# GrblPi_B.net
KiCad netlist of a schematic drawn in EAGLE
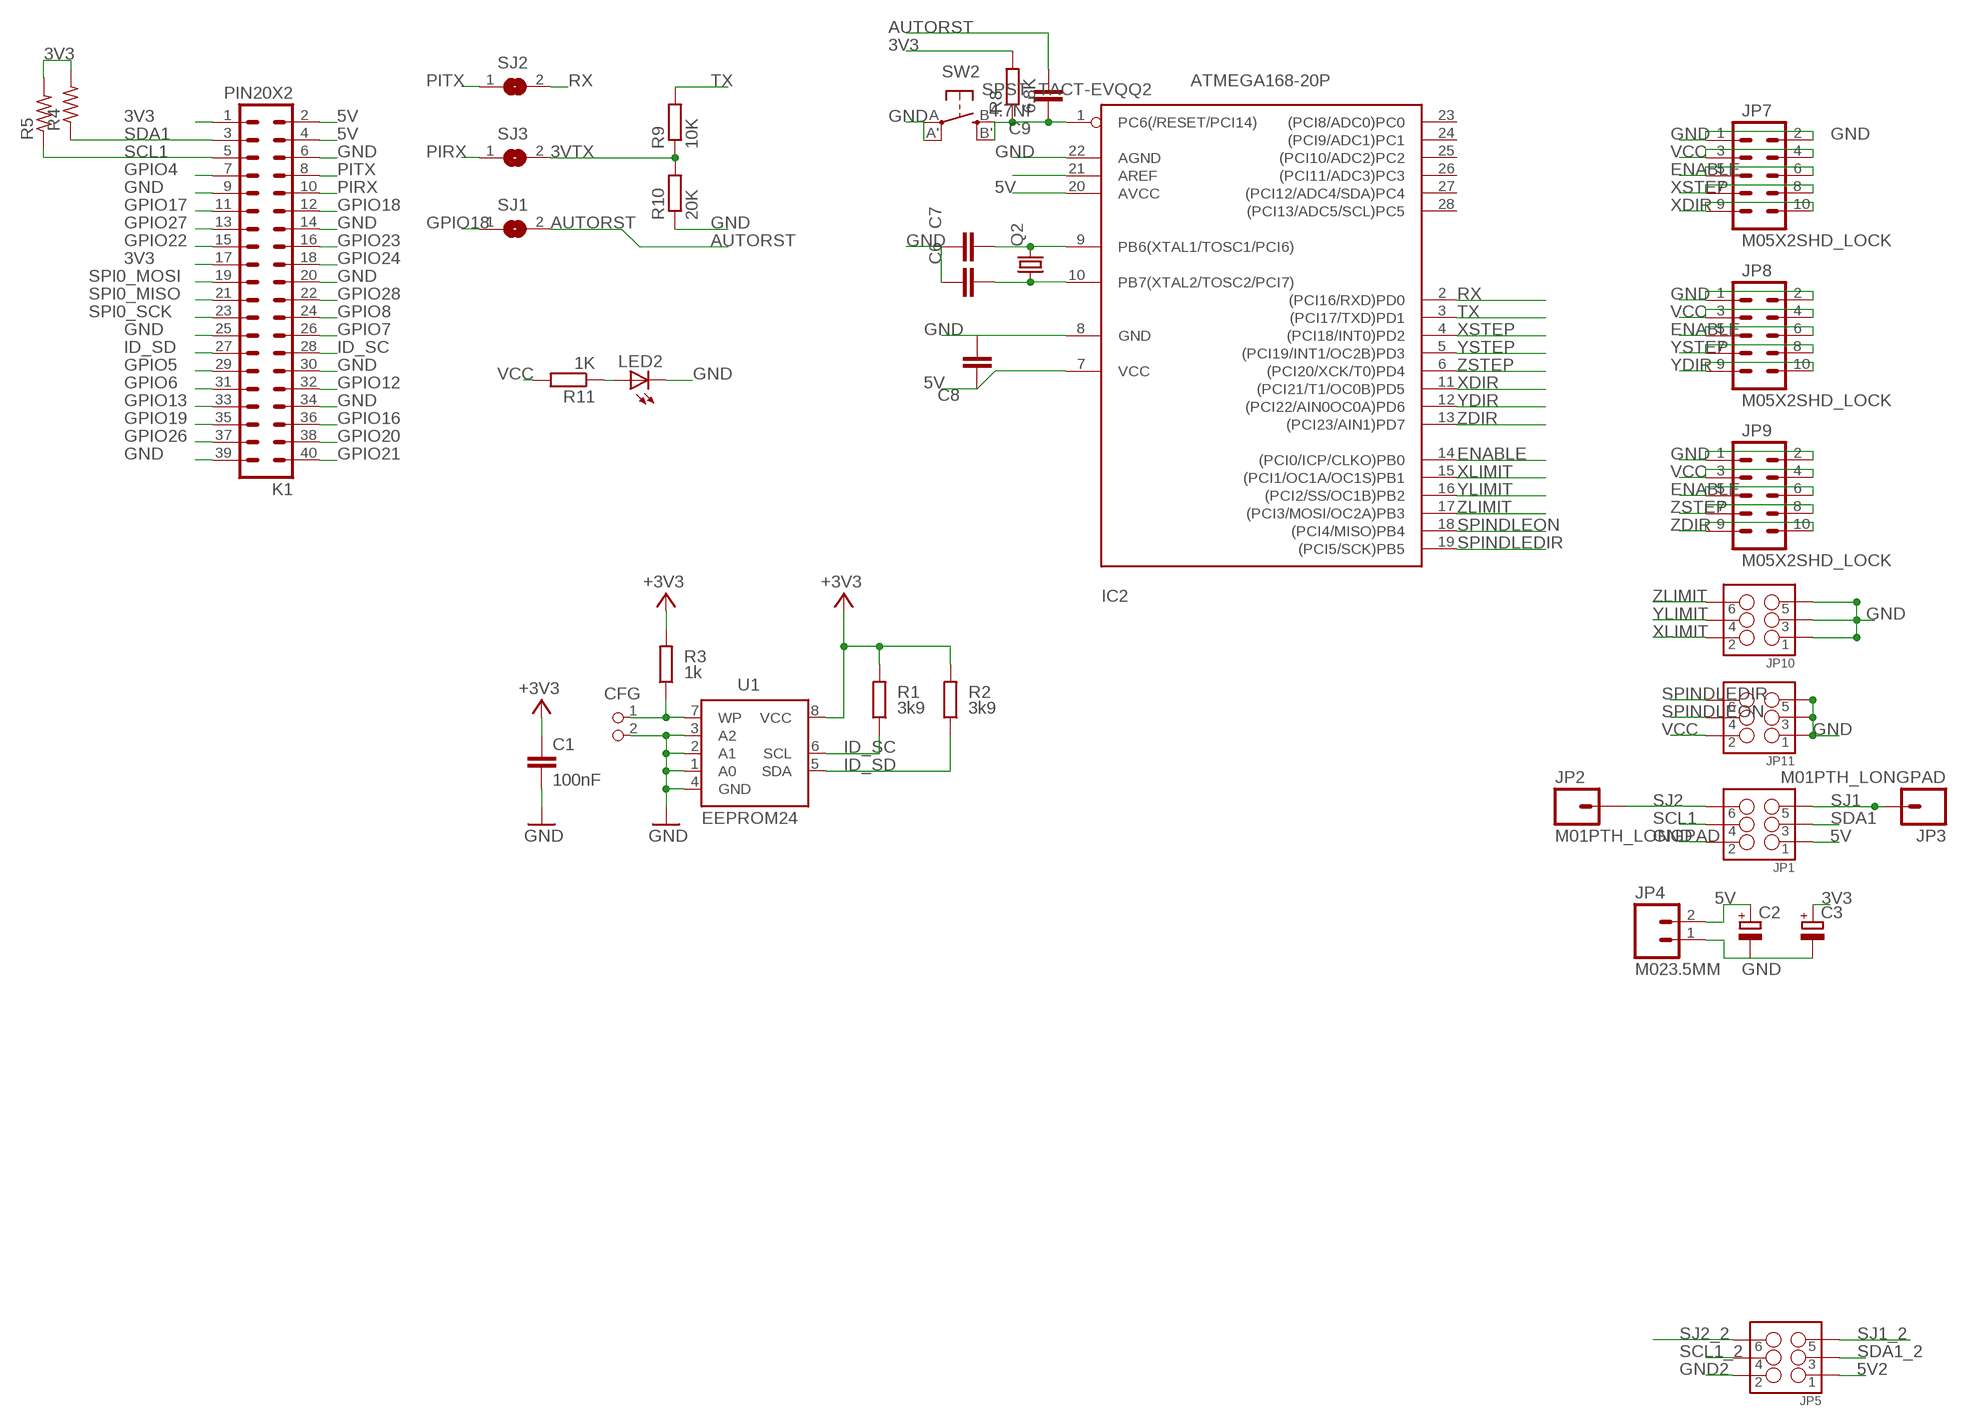
[diagram p0: schematic, sheet 1, part 1 of 2]
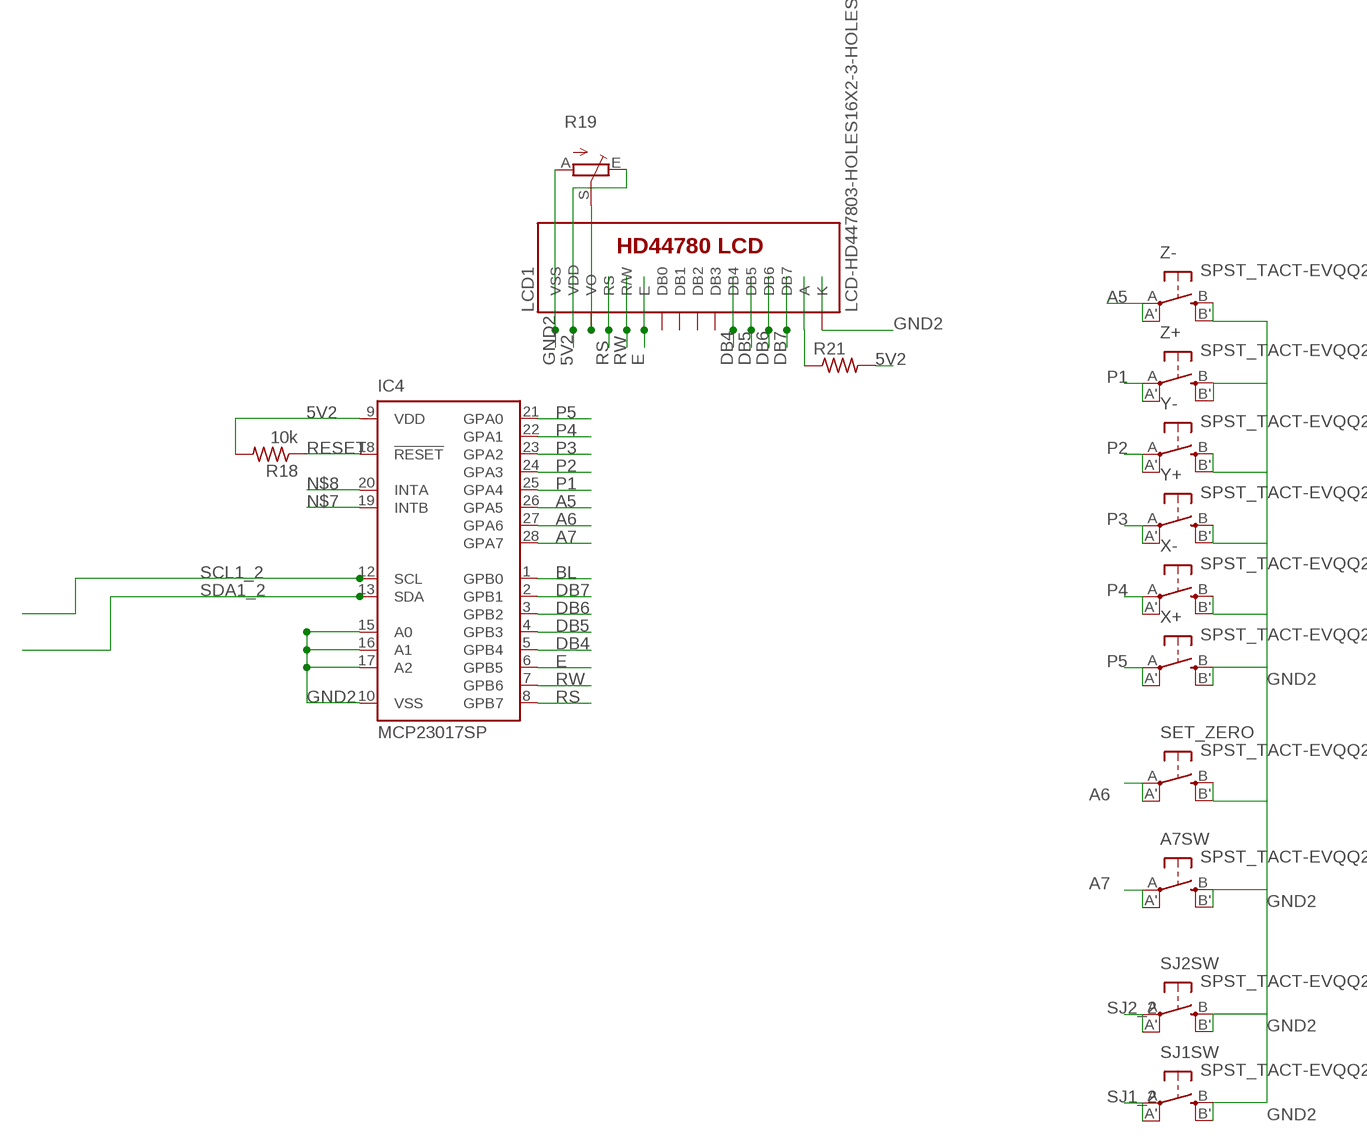
[diagram p1: schematic, sheet 1, part 2 of 2]

(export (version "E")
  (design (tool "Eeschema 10.0.6"))
  (components
    (comp (ref "A7SW")
      (value "SPST_TACT-EVQQ2")
      (footprint "eagle-import:EVQ-Q2")
      (libsource (lib "eagle-import") (part "SPST_TACT-EVQQ2"))
    )
    (comp (ref "C1")
      (value "100nF")
      (footprint "eagle-import:C1206")
      (libsource (lib "eagle-import") (part "C-EUC1206"))
    )
    (comp (ref "C2")
      (value "CPOL-EU153CLV-0405")
      (footprint "eagle-import:153CLV-0405")
      (libsource (lib "eagle-import") (part "CPOL-EU153CLV-0405"))
    )
    (comp (ref "C3")
      (value "CPOL-EU153CLV-0405")
      (footprint "eagle-import:153CLV-0405")
      (libsource (lib "eagle-import") (part "CPOL-EU153CLV-0405"))
    )
    (comp (ref "C6")
      (value "CAPACITOR_NPOL-1206")
      (footprint "eagle-import:C1206")
      (libsource (lib "eagle-import") (part "CAPACITOR_NPOL-1206"))
    )
    (comp (ref "C7")
      (value "CAPACITOR_NPOL-1206")
      (footprint "eagle-import:C1206")
      (libsource (lib "eagle-import") (part "CAPACITOR_NPOL-1206"))
    )
    (comp (ref "C8")
      (value "CAPACITOR_NPOL-1206")
      (footprint "eagle-import:C1206")
      (libsource (lib "eagle-import") (part "CAPACITOR_NPOL-1206"))
    )
    (comp (ref "C9")
      (value "4.7Nf")
      (footprint "eagle-import:C1206")
      (libsource (lib "eagle-import") (part "CAPACITOR_NPOL-1206"))
    )
    (comp (ref "CFG")
      (value "PIN2_100")
      (footprint "eagle-import:PIN_W_2")
      (libsource (lib "eagle-import") (part "PIN2_100"))
    )
    (comp (ref "IC2")
      (value "ATMEGA168-20P")
      (footprint "eagle-import:DIL28-3")
      (libsource (lib "eagle-import") (part "ATMEGA168P-20"))
    )
    (comp (ref "IC4")
      (value "MCP23017SP")
      (footprint "eagle-import:DIL28-3")
      (libsource (lib "eagle-import") (part "MCP23017SP"))
    )
    (comp (ref "JP1")
      (value "M03X2SHROUD")
      (footprint "eagle-import:2X3-SHROUDED")
      (libsource (lib "eagle-import") (part "M03X2SHROUD"))
    )
    (comp (ref "JP2")
      (value "M01PTH_LONGPAD")
      (footprint "eagle-import:1X01_LONGPAD")
      (libsource (lib "eagle-import") (part "M01PTH_LONGPAD"))
    )
    (comp (ref "JP3")
      (value "M01PTH_LONGPAD")
      (footprint "eagle-import:1X01_LONGPAD")
      (libsource (lib "eagle-import") (part "M01PTH_LONGPAD"))
    )
    (comp (ref "JP4")
      (value "M023.5MM")
      (footprint "eagle-import:SCREWTERMINAL-3.5MM-2")
      (libsource (lib "eagle-import") (part "M023.5MM"))
    )
    (comp (ref "JP5")
      (value "M03X2SHROUD")
      (footprint "eagle-import:2X3-SHROUDED")
      (libsource (lib "eagle-import") (part "M03X2SHROUD"))
    )
    (comp (ref "JP7")
      (value "M05X2SHD_LOCK")
      (footprint "eagle-import:2X5-SHROUDED_LOCK")
      (libsource (lib "eagle-import") (part "M05X2SHD_LOCK"))
    )
    (comp (ref "JP8")
      (value "M05X2SHD_LOCK")
      (footprint "eagle-import:2X5-SHROUDED_LOCK")
      (libsource (lib "eagle-import") (part "M05X2SHD_LOCK"))
    )
    (comp (ref "JP9")
      (value "M05X2SHD_LOCK")
      (footprint "eagle-import:2X5-SHROUDED_LOCK")
      (libsource (lib "eagle-import") (part "M05X2SHD_LOCK"))
    )
    (comp (ref "JP10")
      (value "M03X2SHROUD")
      (footprint "eagle-import:2X3-SHROUDED")
      (libsource (lib "eagle-import") (part "M03X2SHROUD"))
    )
    (comp (ref "JP11")
      (value "M03X2SHROUD")
      (footprint "eagle-import:2X3-SHROUDED")
      (libsource (lib "eagle-import") (part "M03X2SHROUD"))
    )
    (comp (ref "K1")
      (value "PIN20X2")
      (footprint "eagle-import:PIN_20X2")
      (libsource (lib "eagle-import") (part "PIN20X2"))
    )
    (comp (ref "LCD1")
      (value "LCD-HD447803-HOLES16X2-3-HOLES")
      (footprint "eagle-import:LCD-16X2-3HOLES")
      (libsource (lib "eagle-import") (part "LCD-HD4478016X2-3-HOLES3-HOLES"))
    )
    (comp (ref "LED2")
      (value "LEDCHIPLED_1206")
      (footprint "eagle-import:CHIPLED_1206")
      (libsource (lib "eagle-import") (part "LEDCHIPLED_1206"))
    )
    (comp (ref "Q2")
      (value "CRYSTALHC49UP")
      (footprint "eagle-import:HC49UP")
      (libsource (lib "eagle-import") (part "CRYSTALHC49UP"))
    )
    (comp (ref "R1")
      (value "3k9")
      (footprint "eagle-import:M1206")
      (fields (field (name "TOLERANCE") "5%"))
      (libsource (lib "eagle-import") (part "R-EU_M1206"))
    )
    (comp (ref "R2")
      (value "3k9")
      (footprint "eagle-import:M1206")
      (fields (field (name "TOLERANCE") "5%"))
      (libsource (lib "eagle-import") (part "R-EU_M1206"))
    )
    (comp (ref "R3")
      (value "1k")
      (footprint "eagle-import:M1206")
      (fields (field (name "TOLERANCE") "5%"))
      (libsource (lib "eagle-import") (part "R-EU_M1206"))
    )
    (comp (ref "R4")
      (value "R-US_M1206")
      (footprint "eagle-import:M1206")
      (libsource (lib "eagle-import") (part "R-US_M1206"))
    )
    (comp (ref "R5")
      (value "R-US_M1206")
      (footprint "eagle-import:M1206")
      (libsource (lib "eagle-import") (part "R-US_M1206"))
    )
    (comp (ref "R8")
      (value "6.8K")
      (footprint "eagle-import:R1206")
      (libsource (lib "eagle-import") (part "RESISTOR-1206"))
    )
    (comp (ref "R9")
      (value "10K")
      (footprint "eagle-import:R1206")
      (libsource (lib "eagle-import") (part "RESISTOR-1206"))
    )
    (comp (ref "R10")
      (value "20K")
      (footprint "eagle-import:R1206")
      (libsource (lib "eagle-import") (part "RESISTOR-1206"))
    )
    (comp (ref "R11")
      (value "1K")
      (footprint "eagle-import:R1206")
      (libsource (lib "eagle-import") (part "RESISTOR-1206"))
    )
    (comp (ref "R18")
      (value "10k")
      (footprint "eagle-import:M1206")
      (libsource (lib "eagle-import") (part "R-US_M1206"))
    )
    (comp (ref "R19")
      (value "TRIM_EU-CA6V")
      (footprint "eagle-import:CA6V")
      (libsource (lib "eagle-import") (part "TRIM_EU-CA6V"))
    )
    (comp (ref "R21")
      (value "R-US_M1206")
      (footprint "eagle-import:M1206")
      (libsource (lib "eagle-import") (part "R-US_M1206"))
    )
    (comp (ref "SET_ZERO")
      (value "SPST_TACT-EVQQ2")
      (footprint "eagle-import:EVQ-Q2")
      (libsource (lib "eagle-import") (part "SPST_TACT-EVQQ2"))
    )
    (comp (ref "SJ1") (value "SJ") (footprint "eagle-import:SJ") (libsource (lib "eagle-import") (part "SJ")))
    (comp (ref "SJ1SW")
      (value "SPST_TACT-EVQQ2")
      (footprint "eagle-import:EVQ-Q2")
      (libsource (lib "eagle-import") (part "SPST_TACT-EVQQ2"))
    )
    (comp (ref "SJ2") (value "SJ") (footprint "eagle-import:SJ") (libsource (lib "eagle-import") (part "SJ")))
    (comp (ref "SJ2SW")
      (value "SPST_TACT-EVQQ2")
      (footprint "eagle-import:EVQ-Q2")
      (libsource (lib "eagle-import") (part "SPST_TACT-EVQQ2"))
    )
    (comp (ref "SJ3") (value "SJ") (footprint "eagle-import:SJ") (libsource (lib "eagle-import") (part "SJ")))
    (comp (ref "SW2")
      (value "SPST_TACT-EVQQ2")
      (footprint "eagle-import:EVQ-Q2")
      (libsource (lib "eagle-import") (part "SPST_TACT-EVQQ2"))
    )
    (comp (ref "U1")
      (value "EEPROM24")
      (footprint "eagle-import:SOIC8")
      (libsource (lib "eagle-import") (part "EEPROM24"))
    )
    (comp (ref "X+")
      (value "SPST_TACT-EVQQ2")
      (footprint "eagle-import:EVQ-Q2")
      (libsource (lib "eagle-import") (part "SPST_TACT-EVQQ2"))
    )
    (comp (ref "X-")
      (value "SPST_TACT-EVQQ2")
      (footprint "eagle-import:EVQ-Q2")
      (libsource (lib "eagle-import") (part "SPST_TACT-EVQQ2"))
    )
    (comp (ref "Y+")
      (value "SPST_TACT-EVQQ2")
      (footprint "eagle-import:EVQ-Q2")
      (libsource (lib "eagle-import") (part "SPST_TACT-EVQQ2"))
    )
    (comp (ref "Y-")
      (value "SPST_TACT-EVQQ2")
      (footprint "eagle-import:EVQ-Q2")
      (libsource (lib "eagle-import") (part "SPST_TACT-EVQQ2"))
    )
    (comp (ref "Z+")
      (value "SPST_TACT-EVQQ2")
      (footprint "eagle-import:EVQ-Q2")
      (libsource (lib "eagle-import") (part "SPST_TACT-EVQQ2"))
    )
    (comp (ref "Z-")
      (value "SPST_TACT-EVQQ2")
      (footprint "eagle-import:EVQ-Q2")
      (libsource (lib "eagle-import") (part "SPST_TACT-EVQQ2"))
    )
  )
  (nets
    (net (code "1") (name "+3V3") (class "Default")
      (node (ref "C1") (pin "1") (pinfunction "1_1") (pintype "passive"))
      (node (ref "R1") (pin "2") (pinfunction "2_2") (pintype "passive"))
      (node (ref "R2") (pin "2") (pinfunction "2_2") (pintype "passive"))
      (node (ref "R3") (pin "2") (pinfunction "2_2") (pintype "passive"))
      (node (ref "U1") (pin "8") (pinfunction "VCC_8") (pintype "power_in"))
    )
    (net (code "2") (name "/3V3") (class "Default")
      (node (ref "C3") (pin "+") (pinfunction "+_+") (pintype "passive"))
      (node (ref "K1") (pin "1") (pinfunction "1_1") (pintype "passive"))
      (node (ref "K1") (pin "17") (pinfunction "17_17") (pintype "passive"))
      (node (ref "R4") (pin "2") (pinfunction "2_2") (pintype "passive"))
      (node (ref "R5") (pin "2") (pinfunction "2_2") (pintype "passive"))
      (node (ref "R8") (pin "2") (pinfunction "2_2") (pintype "passive"))
    )
    (net (code "3") (name "/3VTX") (class "Default")
      (node (ref "R10") (pin "2") (pinfunction "2_2") (pintype "passive"))
      (node (ref "R9") (pin "1") (pinfunction "1_1") (pintype "passive"))
      (node (ref "SJ3") (pin "2") (pinfunction "2_2") (pintype "passive"))
    )
    (net (code "4") (name "/5V") (class "Default")
      (node (ref "C2") (pin "+") (pinfunction "+_+") (pintype "passive"))
      (node (ref "C8") (pin "1") (pinfunction "1_1") (pintype "passive"))
      (node (ref "IC2") (pin "20") (pinfunction "AVCC_20") (pintype "bidirectional"))
      (node (ref "IC2") (pin "7") (pinfunction "VCC_7") (pintype "bidirectional"))
      (node (ref "JP1") (pin "1") (pinfunction "1_1") (pintype "bidirectional"))
      (node (ref "JP4") (pin "2") (pinfunction "2_2") (pintype "passive"))
      (node (ref "K1") (pin "2") (pinfunction "2_2") (pintype "passive"))
      (node (ref "K1") (pin "4") (pinfunction "4_4") (pintype "passive"))
    )
    (net (code "5") (name "/5V2") (class "Default")
      (node (ref "IC4") (pin "9") (pinfunction "VDD_9") (pintype "power_in"))
      (node (ref "JP5") (pin "1") (pinfunction "1_1") (pintype "bidirectional"))
      (node (ref "LCD1") (pin "2") (pinfunction "VDD_2") (pintype "power_in"))
      (node (ref "R18") (pin "2") (pinfunction "2_2") (pintype "passive"))
      (node (ref "R19") (pin "E") (pinfunction "E_E") (pintype "passive"))
      (node (ref "R21") (pin "2") (pinfunction "2_2") (pintype "passive"))
    )
    (net (code "6") (name "/A5") (class "Default")
      (node (ref "IC4") (pin "26") (pinfunction "GPA5_26") (pintype "bidirectional"))
      (node (ref "Z-") (pin "A") (pinfunction "P_A") (pintype "passive"))
      (node (ref "Z-") (pin "A'") (pinfunction "P1_A'") (pintype "passive"))
    )
    (net (code "7") (name "/A6") (class "Default")
      (node (ref "IC4") (pin "27") (pinfunction "GPA6_27") (pintype "bidirectional"))
      (node (ref "SET_ZERO") (pin "A") (pinfunction "P_A") (pintype "passive"))
      (node (ref "SET_ZERO") (pin "A'") (pinfunction "P1_A'") (pintype "passive"))
    )
    (net (code "8") (name "/A7") (class "Default")
      (node (ref "A7SW") (pin "A") (pinfunction "P_A") (pintype "passive"))
      (node (ref "A7SW") (pin "A'") (pinfunction "P1_A'") (pintype "passive"))
      (node (ref "IC4") (pin "28") (pinfunction "GPA7_28") (pintype "bidirectional"))
    )
    (net (code "9") (name "/AUTORST") (class "Default")
      (node (ref "C9") (pin "2") (pinfunction "2_2") (pintype "passive"))
      (node (ref "SJ1") (pin "2") (pinfunction "2_2") (pintype "passive"))
    )
    (net (code "10") (name "/BL") (class "Default")
      (node (ref "IC4") (pin "1") (pinfunction "GPB0_1") (pintype "bidirectional"))
    )
    (net (code "11") (name "/DB4") (class "Default")
      (node (ref "IC4") (pin "5") (pinfunction "GPB4_5") (pintype "bidirectional"))
      (node (ref "LCD1") (pin "11") (pinfunction "DB4_11") (pintype "bidirectional"))
    )
    (net (code "12") (name "/DB5") (class "Default")
      (node (ref "IC4") (pin "4") (pinfunction "GPB3_4") (pintype "bidirectional"))
      (node (ref "LCD1") (pin "12") (pinfunction "DB5_12") (pintype "bidirectional"))
    )
    (net (code "13") (name "/DB6") (class "Default")
      (node (ref "IC4") (pin "3") (pinfunction "GPB2_3") (pintype "bidirectional"))
      (node (ref "LCD1") (pin "13") (pinfunction "DB6_13") (pintype "bidirectional"))
    )
    (net (code "14") (name "/DB7") (class "Default")
      (node (ref "IC4") (pin "2") (pinfunction "GPB1_2") (pintype "bidirectional"))
      (node (ref "LCD1") (pin "14") (pinfunction "DB7_14") (pintype "bidirectional"))
    )
    (net (code "15") (name "/E") (class "Default")
      (node (ref "IC4") (pin "6") (pinfunction "GPB5_6") (pintype "bidirectional"))
      (node (ref "LCD1") (pin "6") (pinfunction "E_6") (pintype "input"))
    )
    (net (code "16") (name "/ENABLE") (class "Default")
      (node (ref "IC2") (pin "14") (pinfunction "(PCI0/ICP/CLKO)PB0_14") (pintype "bidirectional"))
      (node (ref "JP7") (pin "5") (pinfunction "5_5") (pintype "passive"))
      (node (ref "JP7") (pin "6") (pinfunction "6_6") (pintype "passive"))
      (node (ref "JP8") (pin "5") (pinfunction "5_5") (pintype "passive"))
      (node (ref "JP8") (pin "6") (pinfunction "6_6") (pintype "passive"))
      (node (ref "JP9") (pin "5") (pinfunction "5_5") (pintype "passive"))
      (node (ref "JP9") (pin "6") (pinfunction "6_6") (pintype "passive"))
    )
    (net (code "17") (name "/GND2") (class "Default")
      (node (ref "A7SW") (pin "B") (pinfunction "S_B") (pintype "passive"))
      (node (ref "A7SW") (pin "B'") (pinfunction "S1_B'") (pintype "passive"))
      (node (ref "IC4") (pin "10") (pinfunction "VSS_10") (pintype "power_in"))
      (node (ref "IC4") (pin "15") (pinfunction "A0_15") (pintype "input"))
      (node (ref "IC4") (pin "16") (pinfunction "A1_16") (pintype "input"))
      (node (ref "IC4") (pin "17") (pinfunction "A2_17") (pintype "input"))
      (node (ref "JP5") (pin "2") (pinfunction "2_2") (pintype "bidirectional"))
      (node (ref "LCD1") (pin "1") (pinfunction "VSS_1") (pintype "power_in"))
      (node (ref "LCD1") (pin "16") (pinfunction "K_16") (pintype "power_in"))
      (node (ref "R19") (pin "A") (pinfunction "A_A") (pintype "passive"))
      (node (ref "SET_ZERO") (pin "B") (pinfunction "S_B") (pintype "passive"))
      (node (ref "SET_ZERO") (pin "B'") (pinfunction "S1_B'") (pintype "passive"))
      (node (ref "SJ1SW") (pin "B") (pinfunction "S_B") (pintype "passive"))
      (node (ref "SJ1SW") (pin "B'") (pinfunction "S1_B'") (pintype "passive"))
      (node (ref "SJ2SW") (pin "B") (pinfunction "S_B") (pintype "passive"))
      (node (ref "SJ2SW") (pin "B'") (pinfunction "S1_B'") (pintype "passive"))
      (node (ref "X+") (pin "B") (pinfunction "S_B") (pintype "passive"))
      (node (ref "X+") (pin "B'") (pinfunction "S1_B'") (pintype "passive"))
      (node (ref "X-") (pin "B") (pinfunction "S_B") (pintype "passive"))
      (node (ref "X-") (pin "B'") (pinfunction "S1_B'") (pintype "passive"))
      (node (ref "Y+") (pin "B") (pinfunction "S_B") (pintype "passive"))
      (node (ref "Y+") (pin "B'") (pinfunction "S1_B'") (pintype "passive"))
      (node (ref "Y-") (pin "B") (pinfunction "S_B") (pintype "passive"))
      (node (ref "Y-") (pin "B'") (pinfunction "S1_B'") (pintype "passive"))
      (node (ref "Z+") (pin "B") (pinfunction "S_B") (pintype "passive"))
      (node (ref "Z+") (pin "B'") (pinfunction "S1_B'") (pintype "passive"))
      (node (ref "Z-") (pin "B") (pinfunction "S_B") (pintype "passive"))
      (node (ref "Z-") (pin "B'") (pinfunction "S1_B'") (pintype "passive"))
    )
    (net (code "18") (name "/GPIO4") (class "Default")
      (node (ref "K1") (pin "7") (pinfunction "7_7") (pintype "passive"))
    )
    (net (code "19") (name "/GPIO5") (class "Default")
      (node (ref "K1") (pin "29") (pinfunction "29_29") (pintype "passive"))
    )
    (net (code "20") (name "/GPIO6") (class "Default")
      (node (ref "K1") (pin "31") (pinfunction "31_31") (pintype "passive"))
    )
    (net (code "21") (name "/GPIO7") (class "Default")
      (node (ref "K1") (pin "26") (pinfunction "26_26") (pintype "passive"))
    )
    (net (code "22") (name "/GPIO8") (class "Default")
      (node (ref "K1") (pin "24") (pinfunction "24_24") (pintype "passive"))
    )
    (net (code "23") (name "/GPIO12") (class "Default")
      (node (ref "K1") (pin "32") (pinfunction "32_32") (pintype "passive"))
    )
    (net (code "24") (name "/GPIO13") (class "Default")
      (node (ref "K1") (pin "33") (pinfunction "33_33") (pintype "passive"))
    )
    (net (code "25") (name "/GPIO16") (class "Default")
      (node (ref "K1") (pin "36") (pinfunction "36_36") (pintype "passive"))
    )
    (net (code "26") (name "/GPIO17") (class "Default")
      (node (ref "K1") (pin "11") (pinfunction "11_11") (pintype "passive"))
    )
    (net (code "27") (name "/GPIO18") (class "Default")
      (node (ref "K1") (pin "12") (pinfunction "12_12") (pintype "passive"))
      (node (ref "SJ1") (pin "1") (pinfunction "1_1") (pintype "passive"))
    )
    (net (code "28") (name "/GPIO19") (class "Default")
      (node (ref "K1") (pin "35") (pinfunction "35_35") (pintype "passive"))
    )
    (net (code "29") (name "/GPIO20") (class "Default")
      (node (ref "K1") (pin "38") (pinfunction "38_38") (pintype "passive"))
    )
    (net (code "30") (name "/GPIO21") (class "Default")
      (node (ref "K1") (pin "40") (pinfunction "40_40") (pintype "passive"))
    )
    (net (code "31") (name "/GPIO22") (class "Default")
      (node (ref "K1") (pin "15") (pinfunction "15_15") (pintype "passive"))
    )
    (net (code "32") (name "/GPIO23") (class "Default")
      (node (ref "K1") (pin "16") (pinfunction "16_16") (pintype "passive"))
    )
    (net (code "33") (name "/GPIO24") (class "Default")
      (node (ref "K1") (pin "18") (pinfunction "18_18") (pintype "passive"))
    )
    (net (code "34") (name "/GPIO26") (class "Default")
      (node (ref "K1") (pin "37") (pinfunction "37_37") (pintype "passive"))
    )
    (net (code "35") (name "/GPIO27") (class "Default")
      (node (ref "K1") (pin "13") (pinfunction "13_13") (pintype "passive"))
    )
    (net (code "36") (name "/GPIO28") (class "Default")
      (node (ref "K1") (pin "22") (pinfunction "22_22") (pintype "passive"))
    )
    (net (code "37") (name "/ID_SC") (class "Default")
      (node (ref "K1") (pin "28") (pinfunction "28_28") (pintype "passive"))
      (node (ref "R1") (pin "1") (pinfunction "1_1") (pintype "passive"))
      (node (ref "U1") (pin "6") (pinfunction "SCL_6") (pintype "input"))
    )
    (net (code "38") (name "/ID_SD") (class "Default")
      (node (ref "K1") (pin "27") (pinfunction "27_27") (pintype "passive"))
      (node (ref "R2") (pin "1") (pinfunction "1_1") (pintype "passive"))
      (node (ref "U1") (pin "5") (pinfunction "SDA_5") (pintype "bidirectional"))
    )
    (net (code "39") (name "/N$7") (class "Default")
      (node (ref "IC4") (pin "19") (pinfunction "INTB_19") (pintype "output"))
    )
    (net (code "40") (name "/N$8") (class "Default")
      (node (ref "IC4") (pin "20") (pinfunction "INTA_20") (pintype "output"))
    )
    (net (code "41") (name "/P1") (class "Default")
      (node (ref "IC4") (pin "25") (pinfunction "GPA4_25") (pintype "bidirectional"))
      (node (ref "Z+") (pin "A") (pinfunction "P_A") (pintype "passive"))
      (node (ref "Z+") (pin "A'") (pinfunction "P1_A'") (pintype "passive"))
    )
    (net (code "42") (name "/P2") (class "Default")
      (node (ref "IC4") (pin "24") (pinfunction "GPA3_24") (pintype "bidirectional"))
      (node (ref "Y-") (pin "A") (pinfunction "P_A") (pintype "passive"))
      (node (ref "Y-") (pin "A'") (pinfunction "P1_A'") (pintype "passive"))
    )
    (net (code "43") (name "/P3") (class "Default")
      (node (ref "IC4") (pin "23") (pinfunction "GPA2_23") (pintype "bidirectional"))
      (node (ref "Y+") (pin "A") (pinfunction "P_A") (pintype "passive"))
      (node (ref "Y+") (pin "A'") (pinfunction "P1_A'") (pintype "passive"))
    )
    (net (code "44") (name "/P4") (class "Default")
      (node (ref "IC4") (pin "22") (pinfunction "GPA1_22") (pintype "bidirectional"))
      (node (ref "X-") (pin "A") (pinfunction "P_A") (pintype "passive"))
      (node (ref "X-") (pin "A'") (pinfunction "P1_A'") (pintype "passive"))
    )
    (net (code "45") (name "/P5") (class "Default")
      (node (ref "IC4") (pin "21") (pinfunction "GPA0_21") (pintype "bidirectional"))
      (node (ref "X+") (pin "A") (pinfunction "P_A") (pintype "passive"))
      (node (ref "X+") (pin "A'") (pinfunction "P1_A'") (pintype "passive"))
    )
    (net (code "46") (name "/PIRX") (class "Default")
      (node (ref "K1") (pin "10") (pinfunction "10_10") (pintype "passive"))
      (node (ref "SJ3") (pin "1") (pinfunction "1_1") (pintype "passive"))
    )
    (net (code "47") (name "/PITX") (class "Default")
      (node (ref "K1") (pin "8") (pinfunction "8_8") (pintype "passive"))
      (node (ref "SJ2") (pin "1") (pinfunction "1_1") (pintype "passive"))
    )
    (net (code "48") (name "/RESET") (class "Default")
      (node (ref "IC4") (pin "18") (pinfunction "~{RESET}_18") (pintype "input"))
      (node (ref "R18") (pin "1") (pinfunction "1_1") (pintype "passive"))
    )
    (net (code "49") (name "/RS") (class "Default")
      (node (ref "IC4") (pin "8") (pinfunction "GPB7_8") (pintype "bidirectional"))
      (node (ref "LCD1") (pin "4") (pinfunction "RS_4") (pintype "input"))
    )
    (net (code "50") (name "/RW") (class "Default")
      (node (ref "IC4") (pin "7") (pinfunction "GPB6_7") (pintype "bidirectional"))
      (node (ref "LCD1") (pin "5") (pinfunction "R/W_5") (pintype "input"))
    )
    (net (code "51") (name "/RX") (class "Default")
      (node (ref "IC2") (pin "2") (pinfunction "(PCI16/RXD)PD0_2") (pintype "bidirectional"))
      (node (ref "SJ2") (pin "2") (pinfunction "2_2") (pintype "passive"))
    )
    (net (code "52") (name "/SCL1") (class "Default")
      (node (ref "JP1") (pin "4") (pinfunction "4_4") (pintype "bidirectional"))
      (node (ref "K1") (pin "5") (pinfunction "5_5") (pintype "passive"))
      (node (ref "R5") (pin "1") (pinfunction "1_1") (pintype "passive"))
    )
    (net (code "53") (name "/SCL1_2") (class "Default")
      (node (ref "IC4") (pin "12") (pinfunction "SCL_12") (pintype "input"))
      (node (ref "JP5") (pin "4") (pinfunction "4_4") (pintype "bidirectional"))
    )
    (net (code "54") (name "/SDA1") (class "Default")
      (node (ref "JP1") (pin "3") (pinfunction "3_3") (pintype "bidirectional"))
      (node (ref "K1") (pin "3") (pinfunction "3_3") (pintype "passive"))
      (node (ref "R4") (pin "1") (pinfunction "1_1") (pintype "passive"))
    )
    (net (code "55") (name "/SDA1_2") (class "Default")
      (node (ref "IC4") (pin "13") (pinfunction "SDA_13") (pintype "bidirectional"))
      (node (ref "JP5") (pin "3") (pinfunction "3_3") (pintype "bidirectional"))
    )
    (net (code "56") (name "/SJ1") (class "Default")
      (node (ref "JP1") (pin "5") (pinfunction "5_5") (pintype "bidirectional"))
      (node (ref "JP3") (pin "1") (pinfunction "1_1") (pintype "passive"))
    )
    (net (code "57") (name "/SJ1_2") (class "Default")
      (node (ref "JP5") (pin "5") (pinfunction "5_5") (pintype "bidirectional"))
      (node (ref "SJ1SW") (pin "A") (pinfunction "P_A") (pintype "passive"))
      (node (ref "SJ1SW") (pin "A'") (pinfunction "P1_A'") (pintype "passive"))
    )
    (net (code "58") (name "/SJ2") (class "Default")
      (node (ref "JP1") (pin "6") (pinfunction "6_6") (pintype "bidirectional"))
      (node (ref "JP2") (pin "1") (pinfunction "1_1") (pintype "passive"))
    )
    (net (code "59") (name "/SJ2_2") (class "Default")
      (node (ref "JP5") (pin "6") (pinfunction "6_6") (pintype "bidirectional"))
      (node (ref "SJ2SW") (pin "A") (pinfunction "P_A") (pintype "passive"))
      (node (ref "SJ2SW") (pin "A'") (pinfunction "P1_A'") (pintype "passive"))
    )
    (net (code "60") (name "/SPI0_MISO") (class "Default")
      (node (ref "K1") (pin "21") (pinfunction "21_21") (pintype "passive"))
    )
    (net (code "61") (name "/SPI0_MOSI") (class "Default")
      (node (ref "K1") (pin "19") (pinfunction "19_19") (pintype "passive"))
    )
    (net (code "62") (name "/SPI0_SCK") (class "Default")
      (node (ref "K1") (pin "23") (pinfunction "23_23") (pintype "passive"))
    )
    (net (code "63") (name "/SPINDLEDIR") (class "Default")
      (node (ref "IC2") (pin "19") (pinfunction "(PCI5/SCK)PB5_19") (pintype "bidirectional"))
      (node (ref "JP11") (pin "6") (pinfunction "6_6") (pintype "bidirectional"))
    )
    (net (code "64") (name "/SPINDLEON") (class "Default")
      (node (ref "IC2") (pin "18") (pinfunction "(PCI4/MISO)PB4_18") (pintype "bidirectional"))
      (node (ref "JP11") (pin "4") (pinfunction "4_4") (pintype "bidirectional"))
    )
    (net (code "65") (name "/TX") (class "Default")
      (node (ref "IC2") (pin "3") (pinfunction "(PCI17/TXD)PD1_3") (pintype "bidirectional"))
      (node (ref "R9") (pin "2") (pinfunction "2_2") (pintype "passive"))
    )
    (net (code "66") (name "/VCC") (class "Default")
      (node (ref "JP11") (pin "2") (pinfunction "2_2") (pintype "bidirectional"))
      (node (ref "JP7") (pin "3") (pinfunction "3_3") (pintype "passive"))
      (node (ref "JP7") (pin "4") (pinfunction "4_4") (pintype "passive"))
      (node (ref "JP8") (pin "3") (pinfunction "3_3") (pintype "passive"))
      (node (ref "JP8") (pin "4") (pinfunction "4_4") (pintype "passive"))
      (node (ref "JP9") (pin "3") (pinfunction "3_3") (pintype "passive"))
      (node (ref "JP9") (pin "4") (pinfunction "4_4") (pintype "passive"))
      (node (ref "R11") (pin "2") (pinfunction "2_2") (pintype "passive"))
    )
    (net (code "67") (name "/XDIR") (class "Default")
      (node (ref "IC2") (pin "11") (pinfunction "(PCI21/T1/OC0B)PD5_11") (pintype "bidirectional"))
      (node (ref "JP7") (pin "10") (pinfunction "10_10") (pintype "passive"))
      (node (ref "JP7") (pin "9") (pinfunction "9_9") (pintype "passive"))
    )
    (net (code "68") (name "/XLIMIT") (class "Default")
      (node (ref "IC2") (pin "15") (pinfunction "(PCI1/OC1A/OC1S)PB1_15") (pintype "bidirectional"))
      (node (ref "JP10") (pin "2") (pinfunction "2_2") (pintype "bidirectional"))
    )
    (net (code "69") (name "/XSTEP") (class "Default")
      (node (ref "IC2") (pin "4") (pinfunction "(PCI18/INT0)PD2_4") (pintype "bidirectional"))
      (node (ref "JP7") (pin "7") (pinfunction "7_7") (pintype "passive"))
      (node (ref "JP7") (pin "8") (pinfunction "8_8") (pintype "passive"))
    )
    (net (code "70") (name "/YDIR") (class "Default")
      (node (ref "IC2") (pin "12") (pinfunction "(PCI22/AIN0OC0A)PD6_12") (pintype "bidirectional"))
      (node (ref "JP8") (pin "10") (pinfunction "10_10") (pintype "passive"))
      (node (ref "JP8") (pin "9") (pinfunction "9_9") (pintype "passive"))
    )
    (net (code "71") (name "/YLIMIT") (class "Default")
      (node (ref "IC2") (pin "16") (pinfunction "(PCI2/SS/OC1B)PB2_16") (pintype "bidirectional"))
      (node (ref "JP10") (pin "4") (pinfunction "4_4") (pintype "bidirectional"))
    )
    (net (code "72") (name "/YSTEP") (class "Default")
      (node (ref "IC2") (pin "5") (pinfunction "(PCI19/INT1/OC2B)PD3_5") (pintype "bidirectional"))
      (node (ref "JP8") (pin "7") (pinfunction "7_7") (pintype "passive"))
      (node (ref "JP8") (pin "8") (pinfunction "8_8") (pintype "passive"))
    )
    (net (code "73") (name "/ZDIR") (class "Default")
      (node (ref "IC2") (pin "13") (pinfunction "(PCI23/AIN1)PD7_13") (pintype "bidirectional"))
      (node (ref "JP9") (pin "10") (pinfunction "10_10") (pintype "passive"))
      (node (ref "JP9") (pin "9") (pinfunction "9_9") (pintype "passive"))
    )
    (net (code "74") (name "/ZLIMIT") (class "Default")
      (node (ref "IC2") (pin "17") (pinfunction "(PCI3/MOSI/OC2A)PB3_17") (pintype "bidirectional"))
      (node (ref "JP10") (pin "6") (pinfunction "6_6") (pintype "bidirectional"))
    )
    (net (code "75") (name "/ZSTEP") (class "Default")
      (node (ref "IC2") (pin "6") (pinfunction "(PCI20/XCK/T0)PD4_6") (pintype "bidirectional"))
      (node (ref "JP9") (pin "7") (pinfunction "7_7") (pintype "passive"))
      (node (ref "JP9") (pin "8") (pinfunction "8_8") (pintype "passive"))
    )
    (net (code "76") (name "GND") (class "Default")
      (node (ref "C1") (pin "2") (pinfunction "2_2") (pintype "passive"))
      (node (ref "C2") (pin "-") (pinfunction "-_-") (pintype "passive"))
      (node (ref "C3") (pin "-") (pinfunction "-_-") (pintype "passive"))
      (node (ref "C6") (pin "1") (pinfunction "1_1") (pintype "passive"))
      (node (ref "C7") (pin "1") (pinfunction "1_1") (pintype "passive"))
      (node (ref "C8") (pin "2") (pinfunction "2_2") (pintype "passive"))
      (node (ref "CFG") (pin "2") (pinfunction "2_2") (pintype "passive"))
      (node (ref "IC2") (pin "22") (pinfunction "AGND_22") (pintype "bidirectional"))
      (node (ref "IC2") (pin "8") (pinfunction "GND_8") (pintype "bidirectional"))
      (node (ref "JP1") (pin "2") (pinfunction "2_2") (pintype "bidirectional"))
      (node (ref "JP10") (pin "1") (pinfunction "1_1") (pintype "bidirectional"))
      (node (ref "JP10") (pin "3") (pinfunction "3_3") (pintype "bidirectional"))
      (node (ref "JP10") (pin "5") (pinfunction "5_5") (pintype "bidirectional"))
      (node (ref "JP11") (pin "1") (pinfunction "1_1") (pintype "bidirectional"))
      (node (ref "JP11") (pin "3") (pinfunction "3_3") (pintype "bidirectional"))
      (node (ref "JP11") (pin "5") (pinfunction "5_5") (pintype "bidirectional"))
      (node (ref "JP4") (pin "1") (pinfunction "1_1") (pintype "passive"))
      (node (ref "JP7") (pin "1") (pinfunction "1_1") (pintype "passive"))
      (node (ref "JP7") (pin "2") (pinfunction "2_2") (pintype "passive"))
      (node (ref "JP8") (pin "1") (pinfunction "1_1") (pintype "passive"))
      (node (ref "JP8") (pin "2") (pinfunction "2_2") (pintype "passive"))
      (node (ref "JP9") (pin "1") (pinfunction "1_1") (pintype "passive"))
      (node (ref "JP9") (pin "2") (pinfunction "2_2") (pintype "passive"))
      (node (ref "K1") (pin "14") (pinfunction "14_14") (pintype "passive"))
      (node (ref "K1") (pin "20") (pinfunction "20_20") (pintype "passive"))
      (node (ref "K1") (pin "25") (pinfunction "25_25") (pintype "passive"))
      (node (ref "K1") (pin "30") (pinfunction "30_30") (pintype "passive"))
      (node (ref "K1") (pin "34") (pinfunction "34_34") (pintype "passive"))
      (node (ref "K1") (pin "39") (pinfunction "39_39") (pintype "passive"))
      (node (ref "K1") (pin "6") (pinfunction "6_6") (pintype "passive"))
      (node (ref "K1") (pin "9") (pinfunction "9_9") (pintype "passive"))
      (node (ref "LED2") (pin "C") (pinfunction "C_C") (pintype "passive"))
      (node (ref "R10") (pin "1") (pinfunction "1_1") (pintype "passive"))
      (node (ref "SW2") (pin "A") (pinfunction "P_A") (pintype "passive"))
      (node (ref "SW2") (pin "A'") (pinfunction "P1_A'") (pintype "passive"))
      (node (ref "U1") (pin "1") (pinfunction "A0_1") (pintype "input"))
      (node (ref "U1") (pin "2") (pinfunction "A1_2") (pintype "input"))
      (node (ref "U1") (pin "3") (pinfunction "A2_3") (pintype "input"))
      (node (ref "U1") (pin "4") (pinfunction "GND_4") (pintype "power_in"))
    )
    (net (code "77") (name "Net-(IC2-PB6(XTAL1{slash}TOSC1{slash}PCI6))") (class "Default")
      (node (ref "C7") (pin "2") (pinfunction "2_2") (pintype "passive"))
      (node (ref "IC2") (pin "9") (pinfunction "PB6(XTAL1/TOSC1/PCI6)_9") (pintype "bidirectional"))
      (node (ref "Q2") (pin "2") (pinfunction "2_2") (pintype "passive"))
    )
    (net (code "78") (name "Net-(IC2-PB7(XTAL2{slash}TOSC2{slash}PCI7))") (class "Default")
      (node (ref "C6") (pin "2") (pinfunction "2_2") (pintype "passive"))
      (node (ref "IC2") (pin "10") (pinfunction "PB7(XTAL2/TOSC2/PCI7)_10") (pintype "bidirectional"))
      (node (ref "Q2") (pin "1") (pinfunction "1_1") (pintype "passive"))
    )
    (net (code "79") (name "Net-(IC2-PC6({slash}RESET{slash}PCI14))") (class "Default")
      (node (ref "C9") (pin "1") (pinfunction "1_1") (pintype "passive"))
      (node (ref "IC2") (pin "1") (pinfunction "PC6(/RESET/PCI14)_1") (pintype "bidirectional"))
      (node (ref "R8") (pin "1") (pinfunction "1_1") (pintype "passive"))
      (node (ref "SW2") (pin "B") (pinfunction "S_B") (pintype "passive"))
      (node (ref "SW2") (pin "B'") (pinfunction "S1_B'") (pintype "passive"))
    )
    (net (code "80") (name "Net-(LCD1-A)") (class "Default")
      (node (ref "LCD1") (pin "15") (pinfunction "A_15") (pintype "power_in"))
      (node (ref "R21") (pin "1") (pinfunction "1_1") (pintype "passive"))
    )
    (net (code "81") (name "Net-(LCD1-VO)") (class "Default")
      (node (ref "LCD1") (pin "3") (pinfunction "VO_3") (pintype "bidirectional"))
      (node (ref "R19") (pin "S") (pinfunction "S_S") (pintype "passive"))
    )
    (net (code "82") (name "Net-(LED2-PadA)") (class "Default")
      (node (ref "LED2") (pin "A") (pinfunction "A_A") (pintype "passive"))
      (node (ref "R11") (pin "1") (pinfunction "1_1") (pintype "passive"))
    )
    (net (code "83") (name "Net-(U1-WP)") (class "Default")
      (node (ref "CFG") (pin "1") (pinfunction "1_1") (pintype "passive"))
      (node (ref "R3") (pin "1") (pinfunction "1_1") (pintype "passive"))
      (node (ref "U1") (pin "7") (pinfunction "WP_7") (pintype "input"))
    )
    (net (code "84") (name "unconnected-(IC2-(PCI8{slash}ADC0)PC0-Pad23)") (class "Default")
      (node (ref "IC2") (pin "23") (pinfunction "(PCI8/ADC0)PC0_23") (pintype "bidirectional"))
    )
    (net (code "85") (name "unconnected-(IC2-(PCI9{slash}ADC1)PC1-Pad24)") (class "Default")
      (node (ref "IC2") (pin "24") (pinfunction "(PCI9/ADC1)PC1_24") (pintype "bidirectional"))
    )
    (net (code "86") (name "unconnected-(IC2-(PCI10{slash}ADC2)PC2-Pad25)") (class "Default")
      (node (ref "IC2") (pin "25") (pinfunction "(PCI10/ADC2)PC2_25") (pintype "bidirectional"))
    )
    (net (code "87") (name "unconnected-(IC2-(PCI11{slash}ADC3)PC3-Pad26)") (class "Default")
      (node (ref "IC2") (pin "26") (pinfunction "(PCI11/ADC3)PC3_26") (pintype "bidirectional"))
    )
    (net (code "88") (name "unconnected-(IC2-(PCI12{slash}ADC4{slash}SDA)PC4-Pad27)") (class "Default")
      (node (ref "IC2") (pin "27") (pinfunction "(PCI12/ADC4/SDA)PC4_27") (pintype "bidirectional"))
    )
    (net (code "89") (name "unconnected-(IC2-(PCI13{slash}ADC5{slash}SCL)PC5-Pad28)") (class "Default")
      (node (ref "IC2") (pin "28") (pinfunction "(PCI13/ADC5/SCL)PC5_28") (pintype "bidirectional"))
    )
    (net (code "90") (name "unconnected-(IC2-AREF-Pad21)") (class "Default")
      (node (ref "IC2") (pin "21") (pinfunction "AREF_21") (pintype "bidirectional"))
    )
    (net (code "91") (name "unconnected-(LCD1-DB0-Pad7)") (class "Default")
      (node (ref "LCD1") (pin "7") (pinfunction "DB0_7") (pintype "bidirectional"))
    )
    (net (code "92") (name "unconnected-(LCD1-DB1-Pad8)") (class "Default")
      (node (ref "LCD1") (pin "8") (pinfunction "DB1_8") (pintype "bidirectional"))
    )
    (net (code "93") (name "unconnected-(LCD1-DB2-Pad9)") (class "Default")
      (node (ref "LCD1") (pin "9") (pinfunction "DB2_9") (pintype "bidirectional"))
    )
    (net (code "94") (name "unconnected-(LCD1-DB3-Pad10)") (class "Default")
      (node (ref "LCD1") (pin "10") (pinfunction "DB3_10") (pintype "bidirectional"))
    )
  )
)
